# tps610891-boost-to-vin-flashlight-driver.net
KiCad netlist of a schematic drawn in EAGLE
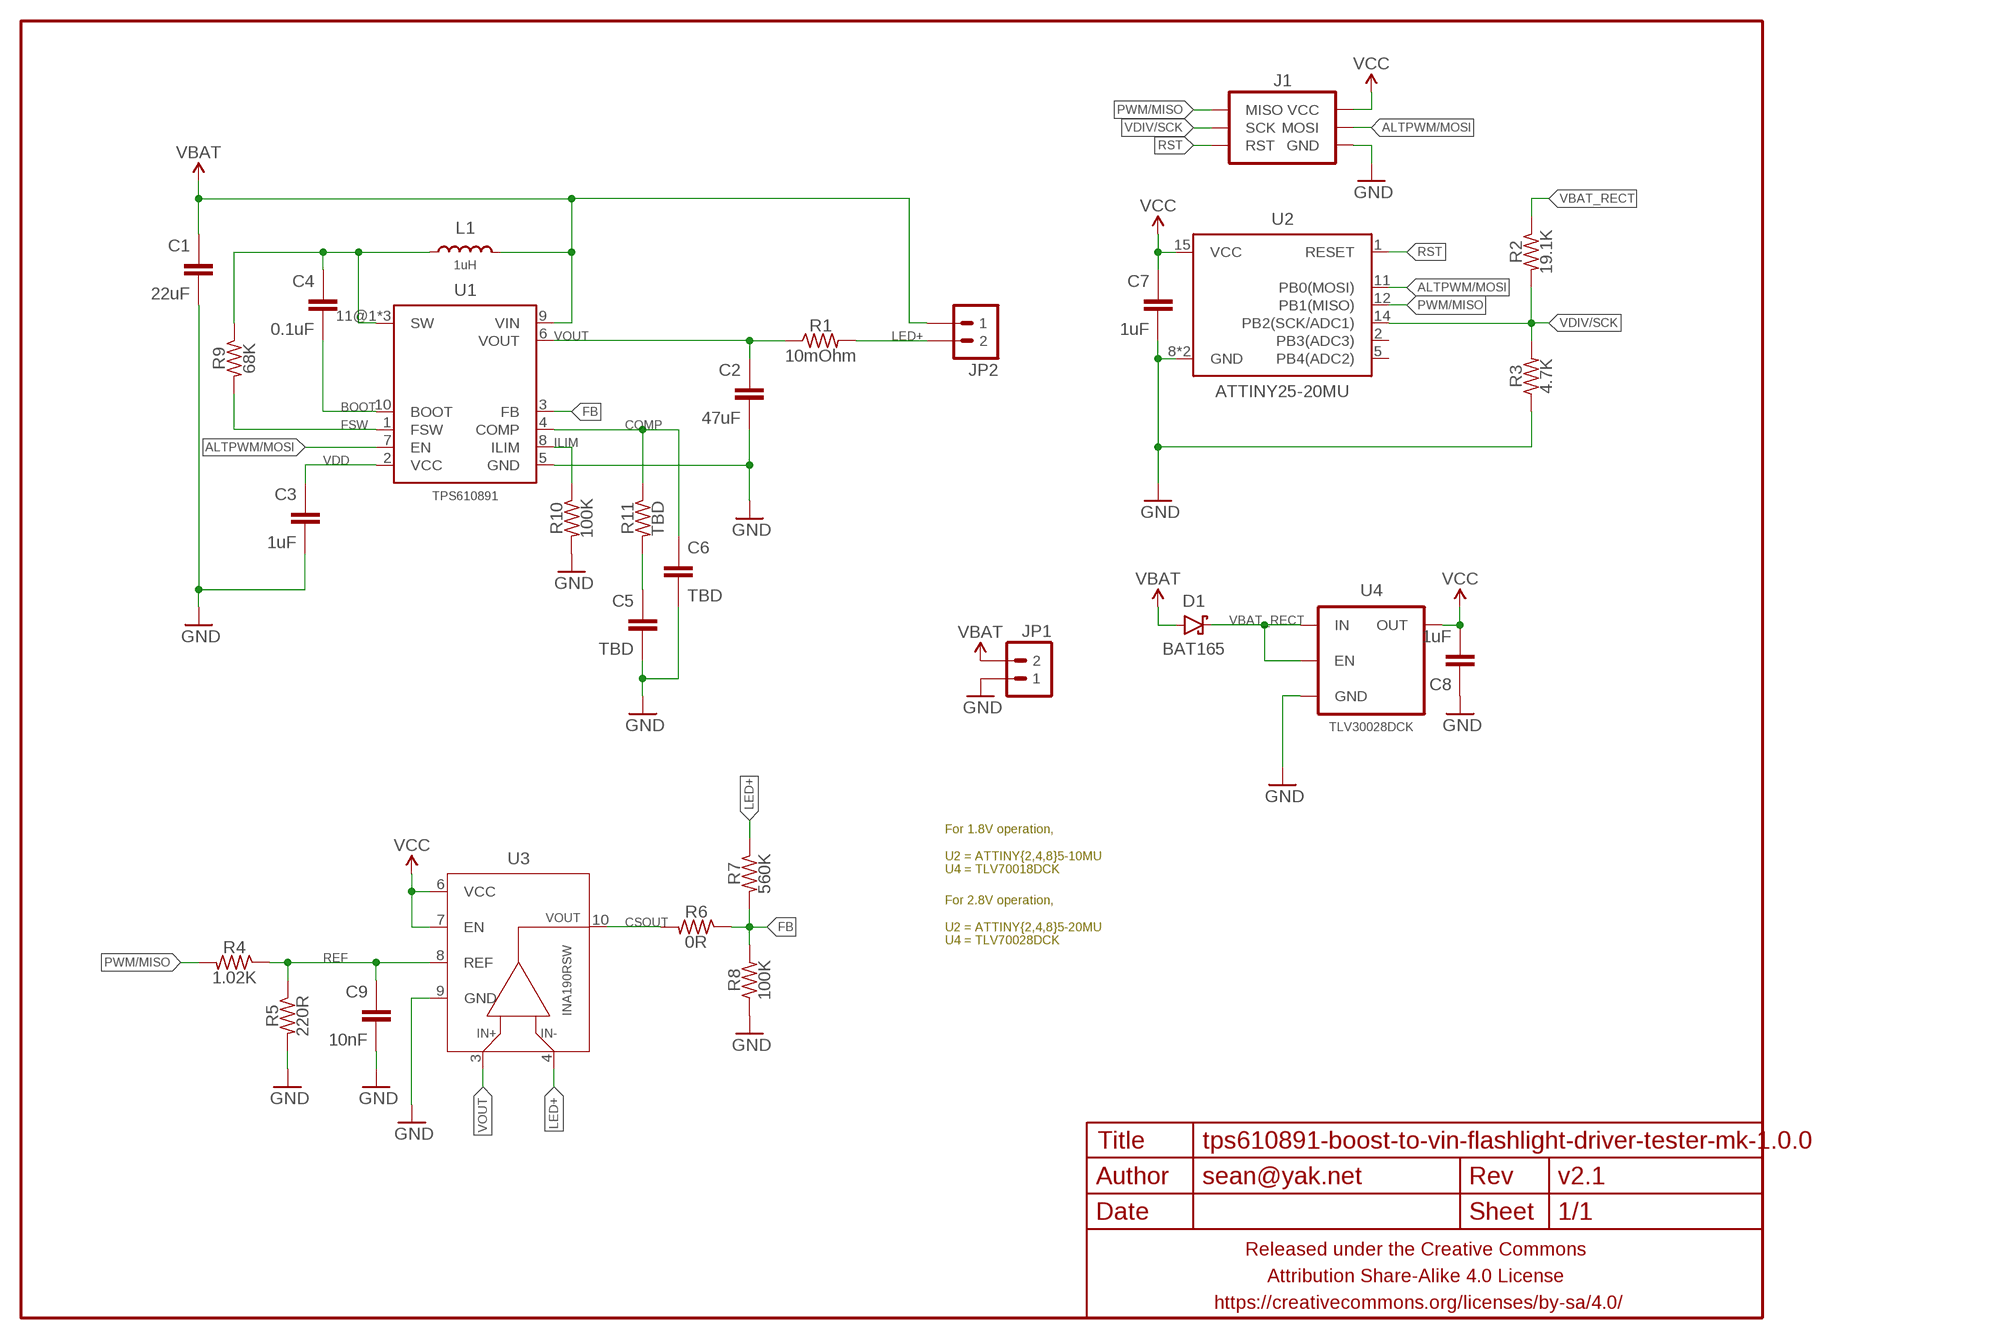
[diagram p0: schematic, sheet 1]

(export (version "E")
  (design (tool "Eeschema 10.0.6"))
  (components
    (comp (ref "C1")
      (value "22uF")
      (footprint "eagle-import:C1206")
      (libsource (lib "eagle-import") (part "CAPACITOR-CERAMICC1206"))
    )
    (comp (ref "C2")
      (value "47uF")
      (footprint "eagle-import:C1206")
      (libsource (lib "eagle-import") (part "CAPACITOR-CERAMICC1206"))
    )
    (comp (ref "C3")
      (value "1uF")
      (footprint "eagle-import:C0402")
      (libsource (lib "eagle-import") (part "CAPACITOR-CERAMICC0402"))
    )
    (comp (ref "C4")
      (value "0.1uF")
      (footprint "eagle-import:C0402")
      (libsource (lib "eagle-import") (part "CAPACITOR-CERAMICC0402"))
    )
    (comp (ref "C5")
      (value "TBD")
      (footprint "eagle-import:C0402")
      (libsource (lib "eagle-import") (part "CAPACITOR-CERAMICC0402"))
    )
    (comp (ref "C6")
      (value "TBD")
      (footprint "eagle-import:C0402")
      (libsource (lib "eagle-import") (part "CAPACITOR-CERAMICC0402"))
    )
    (comp (ref "C7")
      (value "1uF")
      (footprint "eagle-import:C0402")
      (libsource (lib "eagle-import") (part "CAPACITOR-CERAMICC0402"))
    )
    (comp (ref "C8")
      (value "1uF")
      (footprint "eagle-import:C0402")
      (libsource (lib "eagle-import") (part "CAPACITOR-CERAMICC0402"))
    )
    (comp (ref "C9")
      (value "10nF")
      (footprint "eagle-import:C0402")
      (libsource (lib "eagle-import") (part "CAPACITOR-CERAMICC0402"))
    )
    (comp (ref "D1")
      (value "BAT165")
      (footprint "eagle-import:SOD323-SCHOTTKY")
      (libsource (lib "eagle-import") (part "DIODE-SCHOTTKYSOD323"))
    )
    (comp (ref "FRAME1")
      (value "FRAME-LETTERNO_PACKAGE")
      (footprint "eagle-import:DUMMY")
      (fields
        (field (name "DESIGNER") "sean@yak.net")
        (field (name "VERSION") "v2.1")
        (field (name "DESIGNER_1") "sean@yak.net")
        (field (name "VERSION_1") "v2.1")
      )
      (libsource (lib "eagle-import") (part "FRAME-LETTERNO_PACKAGE"))
    )
    (comp (ref "J1")
      (value "AVR_SPI_PRG_6PTH")
      (footprint "eagle-import:2X3")
      (libsource (lib "eagle-import") (part "AVR_SPI_PRG_6PTH"))
    )
    (comp (ref "JP1")
      (value "M021X02_NO_SILK")
      (footprint "eagle-import:1X02_NO_SILK")
      (libsource (lib "eagle-import") (part "M021X02_NO_SILK"))
    )
    (comp (ref "JP2")
      (value "M021X02_NO_SILK")
      (footprint "eagle-import:1X02_NO_SILK")
      (libsource (lib "eagle-import") (part "M021X02_NO_SILK"))
    )
    (comp (ref "L1")
      (value "1uH")
      (footprint "eagle-import:XAL60XX")
      (libsource (lib "eagle-import") (part "INDUCTORXAL60XX"))
    )
    (comp (ref "R1")
      (value "10mOhm")
      (footprint "eagle-import:R1206")
      (libsource (lib "eagle-import") (part "RESISTORR1206"))
    )
    (comp (ref "R2")
      (value "19.1K")
      (footprint "eagle-import:R0402")
      (libsource (lib "eagle-import") (part "RESISTORR0402"))
    )
    (comp (ref "R3")
      (value "4.7K")
      (footprint "eagle-import:R0402")
      (libsource (lib "eagle-import") (part "RESISTORR0402"))
    )
    (comp (ref "R4")
      (value "1.02K")
      (footprint "eagle-import:R0402")
      (libsource (lib "eagle-import") (part "RESISTORR0402"))
    )
    (comp (ref "R5")
      (value "220R")
      (footprint "eagle-import:R0402")
      (libsource (lib "eagle-import") (part "RESISTORR0402"))
    )
    (comp (ref "R6")
      (value "0R")
      (footprint "eagle-import:R0402")
      (libsource (lib "eagle-import") (part "RESISTORR0402"))
    )
    (comp (ref "R7")
      (value "560K")
      (footprint "eagle-import:R0402")
      (libsource (lib "eagle-import") (part "RESISTORR0402"))
    )
    (comp (ref "R8")
      (value "100K")
      (footprint "eagle-import:R0402")
      (libsource (lib "eagle-import") (part "RESISTORR0402"))
    )
    (comp (ref "R9")
      (value "68K")
      (footprint "eagle-import:R0402")
      (libsource (lib "eagle-import") (part "RESISTORR0402"))
    )
    (comp (ref "R10")
      (value "100K")
      (footprint "eagle-import:R0402")
      (libsource (lib "eagle-import") (part "RESISTORR0402"))
    )
    (comp (ref "R11")
      (value "TBD")
      (footprint "eagle-import:R0402")
      (libsource (lib "eagle-import") (part "RESISTORR0402"))
    )
    (comp (ref "U1")
      (value "TPS610891")
      (footprint "eagle-import:VQFN-11")
      (libsource (lib "eagle-import") (part "TPS61089X"))
    )
    (comp (ref "U2")
      (value "ATTINY25-20MU")
      (footprint "eagle-import:QFN20")
      (libsource (lib "eagle-import") (part "ATTINY45TINY85-20-QFN"))
    )
    (comp (ref "U3")
      (value "INA190RSW")
      (footprint "eagle-import:UQFN-10")
      (libsource (lib "eagle-import") (part "INA190RSW"))
    )
    (comp (ref "U4")
      (value "TLV30028DCK")
      (footprint "eagle-import:SC70")
      (libsource (lib "eagle-import") (part "V_REG_ENTLV700XXDCR"))
    )
  )
  (nets
    (net (code "1") (name "/BOOT") (class "Default")
      (node (ref "C4") (pin "2") (pinfunction "2_2") (pintype "passive"))
      (node (ref "U1") (pin "10") (pinfunction "BOOT_10") (pintype "bidirectional"))
    )
    (net (code "2") (name "/COMP") (class "Default")
      (node (ref "C6") (pin "1") (pinfunction "1_1") (pintype "passive"))
      (node (ref "R11") (pin "1") (pinfunction "1_1") (pintype "passive"))
      (node (ref "U1") (pin "4") (pinfunction "COMP_4") (pintype "bidirectional"))
    )
    (net (code "3") (name "/CSOUT") (class "Default")
      (node (ref "R6") (pin "2") (pinfunction "2_2") (pintype "passive"))
      (node (ref "U3") (pin "10") (pinfunction "OUT_10") (pintype "bidirectional"))
    )
    (net (code "4") (name "/FSW") (class "Default")
      (node (ref "R9") (pin "2") (pinfunction "2_2") (pintype "passive"))
      (node (ref "U1") (pin "1") (pinfunction "FSW_1") (pintype "bidirectional"))
    )
    (net (code "5") (name "/ILIM") (class "Default")
      (node (ref "R10") (pin "1") (pinfunction "1_1") (pintype "passive"))
      (node (ref "U1") (pin "8") (pinfunction "ILIM_8") (pintype "bidirectional"))
    )
    (net (code "6") (name "/REF") (class "Default")
      (node (ref "C9") (pin "1") (pinfunction "1_1") (pintype "passive"))
      (node (ref "R4") (pin "1") (pinfunction "1_1") (pintype "passive"))
      (node (ref "R5") (pin "1") (pinfunction "1_1") (pintype "passive"))
      (node (ref "U3") (pin "8") (pinfunction "REF_8") (pintype "bidirectional"))
    )
    (net (code "7") (name "/VDD") (class "Default")
      (node (ref "C3") (pin "1") (pinfunction "1_1") (pintype "passive"))
      (node (ref "U1") (pin "2") (pinfunction "VCC_2") (pintype "bidirectional"))
    )
    (net (code "8") (name "ALTPWM{slash}MOSI") (class "Default")
      (node (ref "J1") (pin "4") (pinfunction "MOSI_4") (pintype "passive"))
      (node (ref "U1") (pin "7") (pinfunction "EN_7") (pintype "bidirectional"))
      (node (ref "U2") (pin "11") (pinfunction "PB0(MOSI)_11") (pintype "bidirectional"))
    )
    (net (code "9") (name "FB") (class "Default")
      (node (ref "R6") (pin "1") (pinfunction "1_1") (pintype "passive"))
      (node (ref "R7") (pin "2") (pinfunction "2_2") (pintype "passive"))
      (node (ref "R8") (pin "2") (pinfunction "2_2") (pintype "passive"))
      (node (ref "U1") (pin "3") (pinfunction "FB_3") (pintype "bidirectional"))
    )
    (net (code "10") (name "GND") (class "Default")
      (node (ref "C1") (pin "2") (pinfunction "2_2") (pintype "passive"))
      (node (ref "C2") (pin "2") (pinfunction "2_2") (pintype "passive"))
      (node (ref "C3") (pin "2") (pinfunction "2_2") (pintype "passive"))
      (node (ref "C5") (pin "2") (pinfunction "2_2") (pintype "passive"))
      (node (ref "C6") (pin "2") (pinfunction "2_2") (pintype "passive"))
      (node (ref "C7") (pin "2") (pinfunction "2_2") (pintype "passive"))
      (node (ref "C8") (pin "1") (pinfunction "1_1") (pintype "passive"))
      (node (ref "C9") (pin "2") (pinfunction "2_2") (pintype "passive"))
      (node (ref "J1") (pin "6") (pinfunction "GND_6") (pintype "passive"))
      (node (ref "JP1") (pin "1") (pinfunction "1_1") (pintype "passive"))
      (node (ref "R10") (pin "2") (pinfunction "2_2") (pintype "passive"))
      (node (ref "R3") (pin "1") (pinfunction "1_1") (pintype "passive"))
      (node (ref "R5") (pin "2") (pinfunction "2_2") (pintype "passive"))
      (node (ref "R8") (pin "1") (pinfunction "1_1") (pintype "passive"))
      (node (ref "U1") (pin "5") (pinfunction "GND_5") (pintype "bidirectional"))
      (node (ref "U2") (pin "8") (pinfunction "GND_8") (pintype "bidirectional"))
      (node (ref "U2") (pin "PAD") (pinfunction "GND_PAD") (pintype "bidirectional"))
      (node (ref "U3") (pin "9") (pinfunction "GND_9") (pintype "bidirectional"))
      (node (ref "U4") (pin "2") (pinfunction "GND_2") (pintype "input"))
    )
    (net (code "11") (name "LED+") (class "Default")
      (node (ref "JP2") (pin "2") (pinfunction "2_2") (pintype "passive"))
      (node (ref "R1") (pin "2") (pinfunction "2_2") (pintype "passive"))
      (node (ref "R7") (pin "1") (pinfunction "1_1") (pintype "passive"))
      (node (ref "U3") (pin "4") (pinfunction "VIN-_4") (pintype "bidirectional"))
    )
    (net (code "12") (name "Net-(C5-Pad1)") (class "Default")
      (node (ref "C5") (pin "1") (pinfunction "1_1") (pintype "passive"))
      (node (ref "R11") (pin "2") (pinfunction "2_2") (pintype "passive"))
    )
    (net (code "13") (name "Net-(L1-1)") (class "Default")
      (node (ref "C4") (pin "1") (pinfunction "1_1") (pintype "passive"))
      (node (ref "L1") (pin "P$1") (pinfunction "1_P$1") (pintype "passive"))
      (node (ref "R9") (pin "1") (pinfunction "1_1") (pintype "passive"))
      (node (ref "U1") (pin "11@1") (pinfunction "SW_11@1") (pintype "bidirectional"))
      (node (ref "U1") (pin "11@2") (pinfunction "SW_11@2") (pintype "bidirectional"))
      (node (ref "U1") (pin "11@3") (pinfunction "SW_11@3") (pintype "bidirectional"))
    )
    (net (code "14") (name "PWM{slash}MISO") (class "Default")
      (node (ref "J1") (pin "1") (pinfunction "MISO_1") (pintype "passive"))
      (node (ref "R4") (pin "2") (pinfunction "2_2") (pintype "passive"))
      (node (ref "U2") (pin "12") (pinfunction "PB1(MISO)_12") (pintype "bidirectional"))
    )
    (net (code "15") (name "RST") (class "Default")
      (node (ref "J1") (pin "5") (pinfunction "RST_5") (pintype "passive"))
      (node (ref "U2") (pin "1") (pinfunction "RESET_1") (pintype "bidirectional"))
    )
    (net (code "16") (name "VBAT") (class "Default")
      (node (ref "C1") (pin "1") (pinfunction "1_1") (pintype "passive"))
      (node (ref "D1") (pin "A") (pinfunction "A_A") (pintype "passive"))
      (node (ref "JP1") (pin "2") (pinfunction "2_2") (pintype "passive"))
      (node (ref "JP2") (pin "1") (pinfunction "1_1") (pintype "passive"))
      (node (ref "L1") (pin "P$2") (pinfunction "2_P$2") (pintype "passive"))
      (node (ref "U1") (pin "9") (pinfunction "VIN_9") (pintype "bidirectional"))
    )
    (net (code "17") (name "VBAT_RECT") (class "Default")
      (node (ref "D1") (pin "C") (pinfunction "C_C") (pintype "passive"))
      (node (ref "R2") (pin "1") (pinfunction "1_1") (pintype "passive"))
      (node (ref "U4") (pin "1") (pinfunction "IN_1") (pintype "input"))
      (node (ref "U4") (pin "3") (pinfunction "EN_3") (pintype "input"))
    )
    (net (code "18") (name "VCC") (class "Default")
      (node (ref "C7") (pin "1") (pinfunction "1_1") (pintype "passive"))
      (node (ref "C8") (pin "2") (pinfunction "2_2") (pintype "passive"))
      (node (ref "J1") (pin "2") (pinfunction "VCC_2") (pintype "passive"))
      (node (ref "U2") (pin "15") (pinfunction "VCC_15") (pintype "bidirectional"))
      (node (ref "U3") (pin "6") (pinfunction "VCC_6") (pintype "bidirectional"))
      (node (ref "U3") (pin "7") (pinfunction "EN_7") (pintype "bidirectional"))
      (node (ref "U4") (pin "5") (pinfunction "OUT_5") (pintype "passive"))
    )
    (net (code "19") (name "VDIV{slash}SCK") (class "Default")
      (node (ref "J1") (pin "3") (pinfunction "SCK_3") (pintype "passive"))
      (node (ref "R2") (pin "2") (pinfunction "2_2") (pintype "passive"))
      (node (ref "R3") (pin "2") (pinfunction "2_2") (pintype "passive"))
      (node (ref "U2") (pin "14") (pinfunction "PB2(SCK/ADC1)_14") (pintype "bidirectional"))
    )
    (net (code "20") (name "VOUT") (class "Default")
      (node (ref "C2") (pin "1") (pinfunction "1_1") (pintype "passive"))
      (node (ref "R1") (pin "1") (pinfunction "1_1") (pintype "passive"))
      (node (ref "U1") (pin "6") (pinfunction "VOUT_6") (pintype "bidirectional"))
      (node (ref "U3") (pin "3") (pinfunction "VIN+_3") (pintype "bidirectional"))
    )
    (net (code "21") (name "unconnected-(U2-PB3(ADC3)-Pad2)") (class "Default")
      (node (ref "U2") (pin "2") (pinfunction "PB3(ADC3)_2") (pintype "bidirectional"))
    )
    (net (code "22") (name "unconnected-(U2-PB4(ADC2)-Pad5)") (class "Default")
      (node (ref "U2") (pin "5") (pinfunction "PB4(ADC2)_5") (pintype "bidirectional"))
    )
  )
)
